# 08_-_Microcontroller.net
KiCad netlist of a schematic drawn in Altium Designer
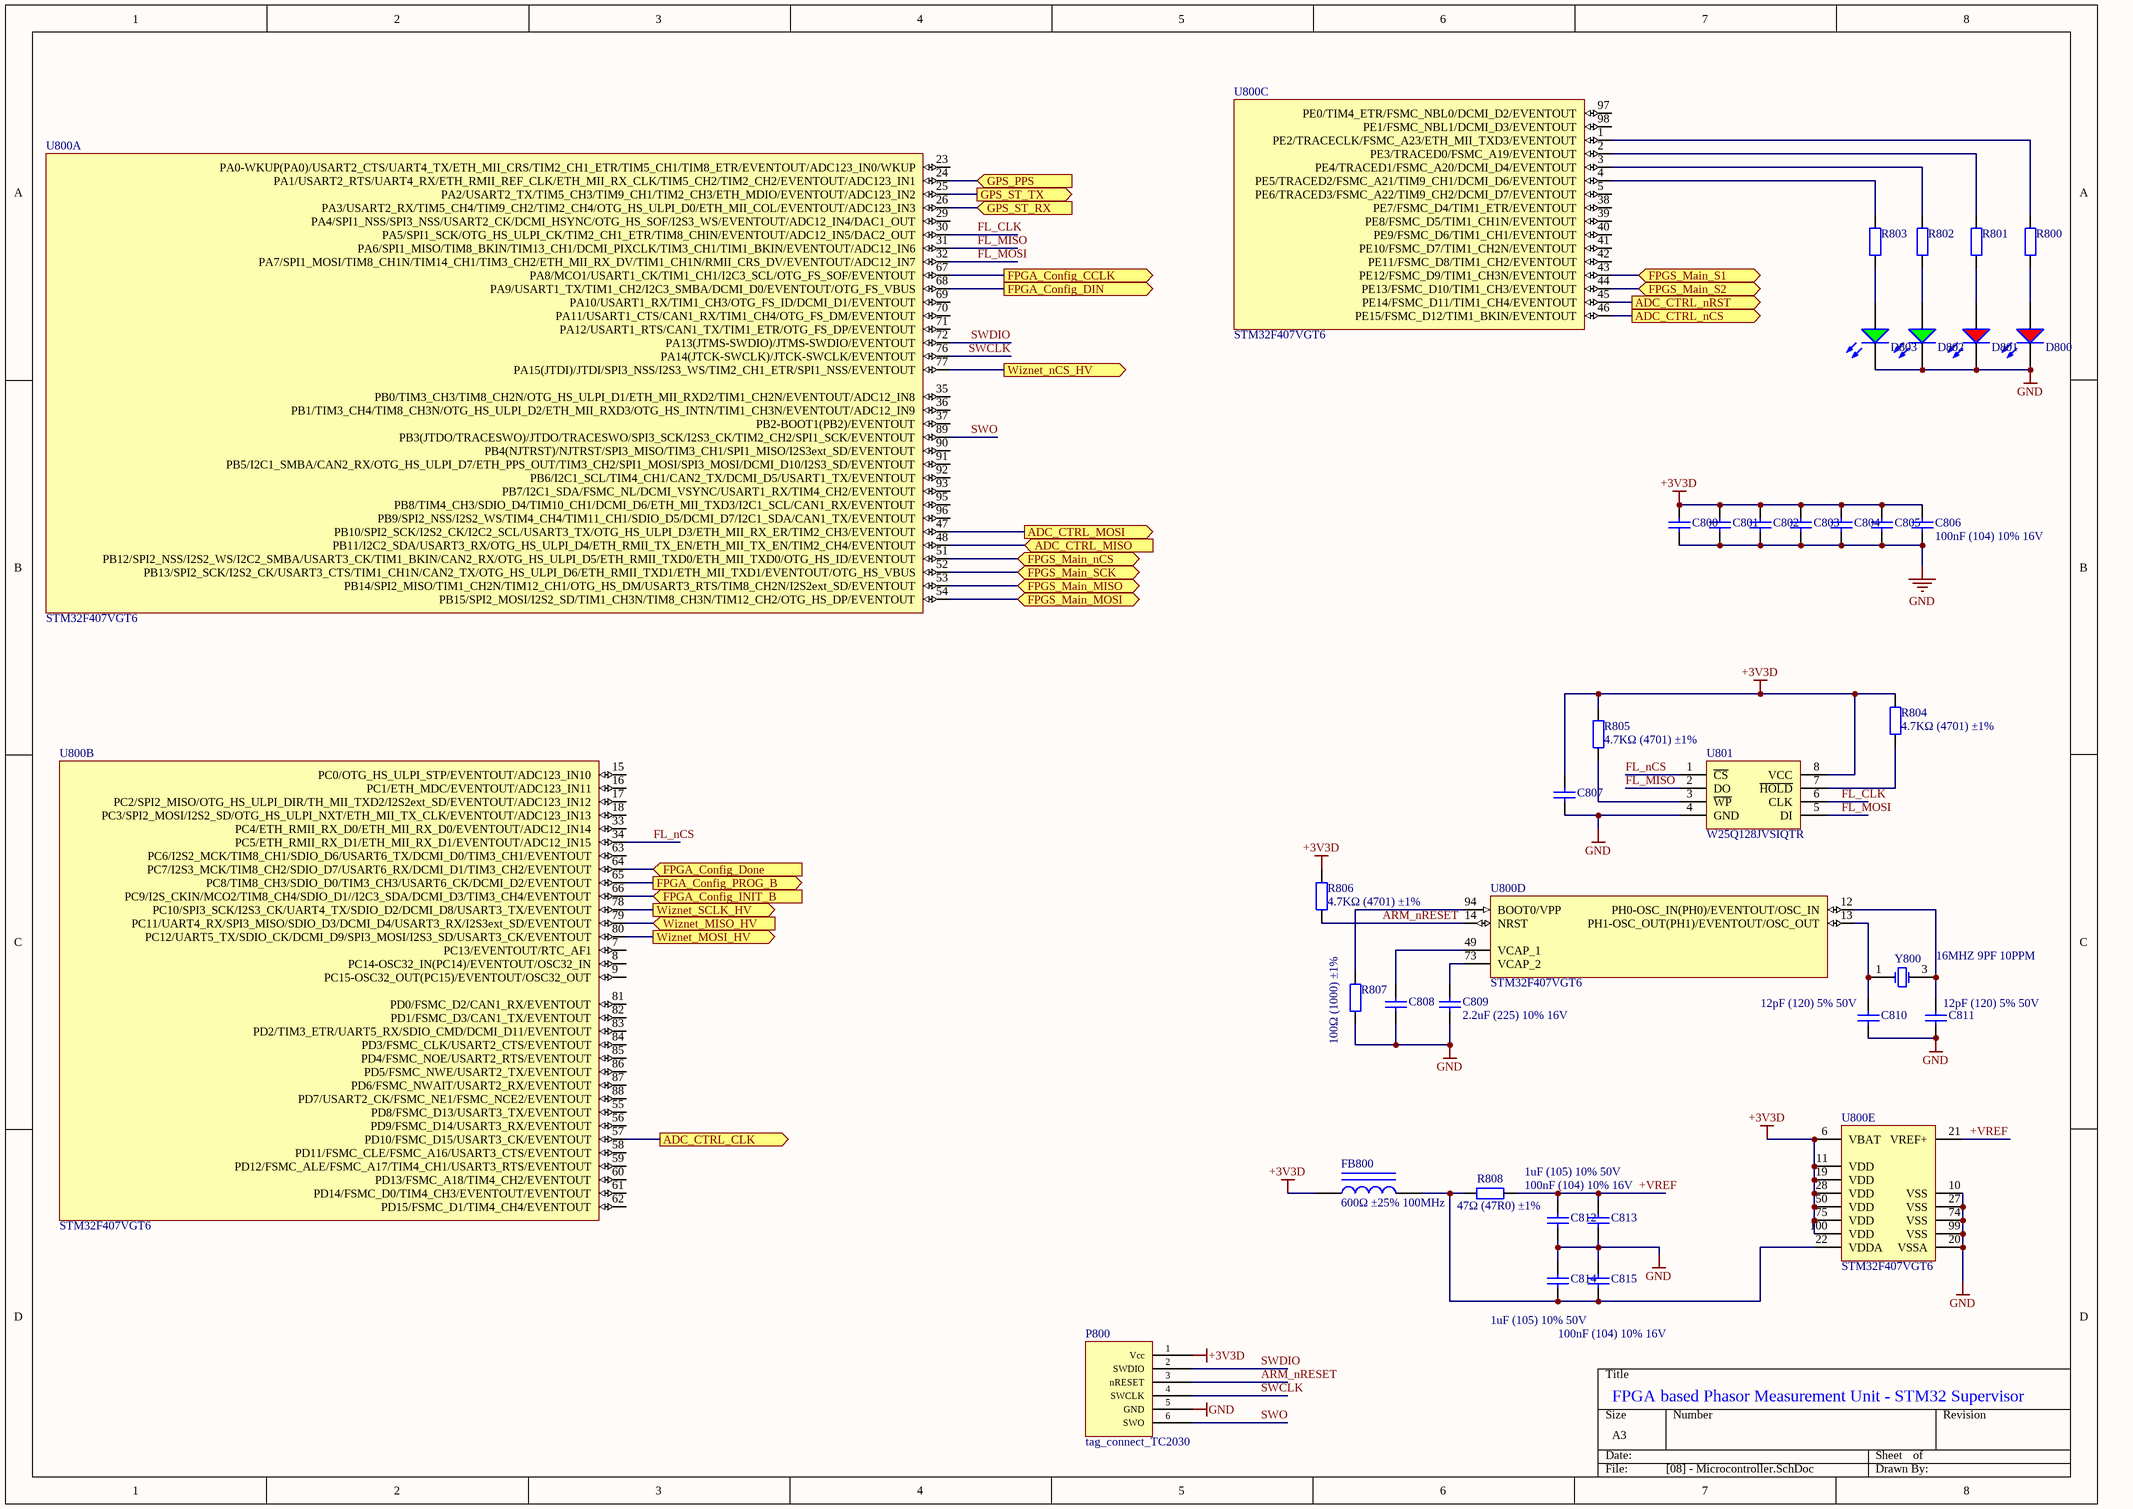
[diagram p0: [08] - Microcontroller.SchDoc]

(export (version "E")
  (design (tool "Eeschema 10.0.6"))
  (components
    (comp (ref "C800")
      (value "100nF (104) 10% 16V")
      (footprint "0402_C")
      (description "贴片电容")
      (libsource (lib "Cap") (part "0402 100nF (104) 10% 16V"))
    )
    (comp (ref "C801")
      (value "100nF (104) 10% 16V")
      (footprint "0402_C")
      (description "贴片电容")
      (libsource (lib "Cap") (part "0402 100nF (104) 10% 16V"))
    )
    (comp (ref "C802")
      (value "100nF (104) 10% 16V")
      (footprint "0402_C")
      (description "贴片电容")
      (libsource (lib "Cap") (part "0402 100nF (104) 10% 16V"))
    )
    (comp (ref "C803")
      (value "100nF (104) 10% 16V")
      (footprint "0402_C")
      (description "贴片电容")
      (libsource (lib "Cap") (part "0402 100nF (104) 10% 16V"))
    )
    (comp (ref "C804")
      (value "100nF (104) 10% 16V")
      (footprint "0402_C")
      (description "贴片电容")
      (libsource (lib "Cap") (part "0402 100nF (104) 10% 16V"))
    )
    (comp (ref "C805")
      (value "100nF (104) 10% 16V")
      (footprint "0402_C")
      (description "贴片电容")
      (libsource (lib "Cap") (part "0402 100nF (104) 10% 16V"))
    )
    (comp (ref "C806")
      (value "100nF (104) 10% 16V")
      (footprint "0402_C")
      (description "贴片电容")
      (libsource (lib "Cap") (part "0402 100nF (104) 10% 16V"))
    )
    (comp (ref "C807")
      (value "100nF (104) 10% 16V")
      (footprint "0402_C")
      (description "贴片电容")
      (libsource (lib "Cap") (part "0402 100nF (104) 10% 16V"))
    )
    (comp (ref "C808")
      (value "2.2uF (225) 10% 16V")
      (footprint "0603_C")
      (description "贴片电容")
      (libsource (lib "Cap") (part "0603 2.2uF (225) 10% 16V"))
    )
    (comp (ref "C809")
      (value "2.2uF (225) 10% 16V")
      (footprint "0603_C")
      (description "贴片电容")
      (libsource (lib "Cap") (part "0603 2.2uF (225) 10% 16V"))
    )
    (comp (ref "C810")
      (value "12pF (120) 5% 50V")
      (footprint "0402_C")
      (description "贴片电容")
      (libsource (lib "Cap") (part "0402 12pF (120) 5% 50V"))
    )
    (comp (ref "C811")
      (value "12pF (120) 5% 50V")
      (footprint "0402_C")
      (description "贴片电容")
      (libsource (lib "Cap") (part "0402 12pF (120) 5% 50V"))
    )
    (comp (ref "C812")
      (value "1uF (105) 10% 50V")
      (footprint "0603_C")
      (description "贴片电容")
      (libsource (lib "Cap") (part "0603 1uF (105) 10% 50V"))
    )
    (comp (ref "C813")
      (value "100nF (104) 10% 16V")
      (footprint "0402_C")
      (description "贴片电容")
      (libsource (lib "Cap") (part "0402 100nF (104) 10% 16V"))
    )
    (comp (ref "C814")
      (value "1uF (105) 10% 50V")
      (footprint "0603_C")
      (description "贴片电容")
      (libsource (lib "Cap") (part "0603 1uF (105) 10% 50V"))
    )
    (comp (ref "C815")
      (value "100nF (104) 10% 16V")
      (footprint "0402_C")
      (description "贴片电容")
      (libsource (lib "Cap") (part "0402 100nF (104) 10% 16V"))
    )
    (comp (ref "D800")
      (value "红灯 0603")
      (footprint "0603_LED_S1")
      (description "发光二极管")
      (libsource (lib "LED") (part "0603 红灯"))
    )
    (comp (ref "D801")
      (value "红灯 0603")
      (footprint "0603_LED_S1")
      (description "发光二极管")
      (libsource (lib "LED") (part "0603 红灯"))
    )
    (comp (ref "D802")
      (value "绿灯 0603")
      (footprint "0603_LED_S1")
      (description "发光二极管")
      (libsource (lib "LED") (part "0603 绿灯"))
    )
    (comp (ref "D803")
      (value "绿灯 0603")
      (footprint "0603_LED_S1")
      (description "发光二极管")
      (libsource (lib "LED") (part "0603 绿灯"))
    )
    (comp (ref "FB800")
      (value "600Ω ±25% 100MHz")
      (footprint "0805_L")
      (description "贴片磁珠")
      (libsource (lib "IUD") (part "0805 600Ω 25% 100MHz"))
    )
    (comp (ref "P800")
      (value "tag_connect_TC2030")
      (footprint "TC2030-MCP-NL")
      (libsource (lib "FPGA_PMU_lib") (part "tag_connect_TC2030"))
    )
    (comp (ref "R800")
      (value "150Ω (1500) ±1%")
      (footprint "0402_R")
      (description "贴片电阻")
      (libsource (lib "RES") (part "0402 150Ω (1500) 1%"))
    )
    (comp (ref "R801")
      (value "150Ω (1500) ±1%")
      (footprint "0402_R")
      (description "贴片电阻")
      (libsource (lib "RES") (part "0402 150Ω (1500) 1%"))
    )
    (comp (ref "R802")
      (value "150Ω (1500) ±1%")
      (footprint "0402_R")
      (description "贴片电阻")
      (libsource (lib "RES") (part "0402 150Ω (1500) 1%"))
    )
    (comp (ref "R803")
      (value "150Ω (1500) ±1%")
      (footprint "0402_R")
      (description "贴片电阻")
      (libsource (lib "RES") (part "0402 150Ω (1500) 1%"))
    )
    (comp (ref "R804")
      (value "4.7KΩ (4701) ±1%")
      (footprint "0402_R")
      (description "贴片电阻")
      (libsource (lib "") (part "0402 4.7KΩ (4701) 1%_1"))
    )
    (comp (ref "R805")
      (value "4.7KΩ (4701) ±1%")
      (footprint "0402_R")
      (description "贴片电阻")
      (libsource (lib "RES") (part "0402 4.7KΩ (4701) 1%"))
    )
    (comp (ref "R806")
      (value "4.7KΩ (4701) ±1%")
      (footprint "0402_R")
      (description "贴片电阻")
      (libsource (lib "") (part "0402 4.7KΩ (4701) 1%_1"))
    )
    (comp (ref "R807")
      (value "100Ω (1000) ±1%")
      (footprint "0402_R")
      (description "贴片电阻")
      (libsource (lib "RES") (part "0402 100Ω (1000) 1%"))
    )
    (comp (ref "R808")
      (value "47Ω (47R0) ±1%")
      (footprint "0402_R")
      (description "贴片电阻")
      (libsource (lib "RES") (part "0402 47Ω (47R0) 1%"))
    )
    (comp (ref "U800")
      (value "STM32F407VGT6")
      (footprint "LQFP-100_14x14x05P")
      (description "ARM")
      (libsource (lib "MCU") (part "STM32F407VGT6"))
    )
    (comp (ref "U801")
      (value "W25Q128JVSIQTR")
      (footprint "SOIC-8_208mil")
      (description "Flash ROM")
      (libsource (lib "IC") (part "W25Q128JVSIQTR_[C97521]"))
    )
    (comp (ref "Y800")
      (value "16MHZ 9PF 10PPM")
      (footprint "SMD-3225_4P")
      (description "贴片晶振")
      (libsource (lib "CrystalOscillator") (part "SMD-3225_4P  16MHZ 9PF 10PPM"))
    )
  )
  (nets
    (net (code "1") (name "+3V3D") (class "Default")
      (node (ref "C800") (pin "2") (pinfunction "2_2") (pintype "passive"))
      (node (ref "C801") (pin "2") (pinfunction "2_2") (pintype "passive"))
      (node (ref "C802") (pin "2") (pinfunction "2_2") (pintype "passive"))
      (node (ref "C803") (pin "2") (pinfunction "2_2") (pintype "passive"))
      (node (ref "C804") (pin "2") (pinfunction "2_2") (pintype "passive"))
      (node (ref "C805") (pin "2") (pinfunction "2_2") (pintype "passive"))
      (node (ref "C806") (pin "2") (pinfunction "2_2") (pintype "passive"))
      (node (ref "C807") (pin "2") (pinfunction "2_2") (pintype "passive"))
      (node (ref "FB800") (pin "1") (pinfunction "1_1") (pintype "passive"))
      (node (ref "P800") (pin "1") (pinfunction "Vcc_1") (pintype "passive"))
      (node (ref "R804") (pin "2") (pinfunction "2_2") (pintype "passive"))
      (node (ref "R805") (pin "1") (pinfunction "1_1") (pintype "passive"))
      (node (ref "R806") (pin "2") (pinfunction "2_2") (pintype "passive"))
      (node (ref "U800") (pin "100") (pinfunction "VDD_100") (pintype "power_in"))
      (node (ref "U800") (pin "11") (pinfunction "VDD_11") (pintype "power_in"))
      (node (ref "U800") (pin "19") (pinfunction "VDD_19") (pintype "power_in"))
      (node (ref "U800") (pin "28") (pinfunction "VDD_28") (pintype "power_in"))
      (node (ref "U800") (pin "50") (pinfunction "VDD_50") (pintype "power_in"))
      (node (ref "U800") (pin "6") (pinfunction "VBAT_6") (pintype "power_in"))
      (node (ref "U800") (pin "75") (pinfunction "VDD_75") (pintype "power_in"))
      (node (ref "U801") (pin "8") (pinfunction "VCC_8") (pintype "passive"))
    )
    (net (code "2") (name "/+VREF") (class "Default")
      (node (ref "C812") (pin "2") (pinfunction "2_2") (pintype "passive"))
      (node (ref "C813") (pin "2") (pinfunction "2_2") (pintype "passive"))
      (node (ref "R808") (pin "2") (pinfunction "2_2") (pintype "passive"))
      (node (ref "U800") (pin "21") (pinfunction "VREF+_21") (pintype "power_in"))
    )
    (net (code "3") (name "/ADC_CTRL_CLK") (class "Default")
      (node (ref "U800") (pin "57") (pinfunction "PD10/FSMC_D15/USART3_CK/EVENTOUT_57") (pintype "bidirectional"))
    )
    (net (code "4") (name "/ADC_CTRL_MISO") (class "Default")
      (node (ref "U800") (pin "48") (pinfunction "PB11/I2C2_SDA/USART3_RX/OTG_HS_ULPI_D4/ETH_RMII_TX_EN/ETH_MII_TX_EN/TIM2_CH4/EVENTOUT_48") (pintype "bidirectional"))
    )
    (net (code "5") (name "/ADC_CTRL_MOSI") (class "Default")
      (node (ref "U800") (pin "47") (pinfunction "PB10/SPI2_SCK/I2S2_CK/I2C2_SCL/USART3_TX/OTG_HS_ULPI_D3/ETH_MII_RX_ER/TIM2_CH3/EVENTOUT_47") (pintype "bidirectional"))
    )
    (net (code "6") (name "/ADC_CTRL_nCS") (class "Default")
      (node (ref "U800") (pin "46") (pinfunction "PE15/FSMC_D12/TIM1_BKIN/EVENTOUT_46") (pintype "bidirectional"))
    )
    (net (code "7") (name "/ADC_CTRL_nRST") (class "Default")
      (node (ref "U800") (pin "45") (pinfunction "PE14/FSMC_D11/TIM1_CH4/EVENTOUT_45") (pintype "bidirectional"))
    )
    (net (code "8") (name "/ARM_nRESET") (class "Default")
      (node (ref "P800") (pin "3") (pinfunction "nRESET_3") (pintype "passive"))
      (node (ref "R806") (pin "1") (pinfunction "1_1") (pintype "passive"))
      (node (ref "U800") (pin "14") (pinfunction "NRST_14") (pintype "bidirectional"))
    )
    (net (code "9") (name "/FL_CLK") (class "Default")
      (node (ref "U800") (pin "30") (pinfunction "PA5/SPI1_SCK/OTG_HS_ULPI_CK/TIM2_CH1_ETR/TIM8_CHIN/EVENTOUT/ADC12_IN5/DAC2_OUT_30") (pintype "bidirectional"))
      (node (ref "U801") (pin "6") (pinfunction "CLK_6") (pintype "passive"))
    )
    (net (code "10") (name "/FL_MISO") (class "Default")
      (node (ref "U800") (pin "31") (pinfunction "PA6/SPI1_MISO/TIM8_BKIN/TIM13_CH1/DCMI_PIXCLK/TIM3_CH1/TIM1_BKIN/EVENTOUT/ADC12_IN6_31") (pintype "bidirectional"))
      (node (ref "U801") (pin "2") (pinfunction "DO_2") (pintype "passive"))
    )
    (net (code "11") (name "/FL_MOSI") (class "Default")
      (node (ref "U800") (pin "32") (pinfunction "PA7/SPI1_MOSI/TIM8_CH1N/TIM14_CH1/TIM3_CH2/ETH_MII_RX_DV/TIM1_CH1N/RMII_CRS_DV/EVENTOUT/ADC12_IN7_32") (pintype "bidirectional"))
      (node (ref "U801") (pin "5") (pinfunction "DI_5") (pintype "passive"))
    )
    (net (code "12") (name "/FL_nCS") (class "Default")
      (node (ref "U800") (pin "34") (pinfunction "PC5/ETH_RMII_RX_D1/ETH_MII_RX_D1/EVENTOUT/ADC12_IN15_34") (pintype "bidirectional"))
      (node (ref "U801") (pin "1") (pinfunction "~{CS}_1") (pintype "passive"))
    )
    (net (code "13") (name "/FPGA_Config_CCLK") (class "Default")
      (node (ref "U800") (pin "67") (pinfunction "PA8/MCO1/USART1_CK/TIM1_CH1/I2C3_SCL/OTG_FS_SOF/EVENTOUT_67") (pintype "bidirectional"))
    )
    (net (code "14") (name "/FPGA_Config_DIN") (class "Default")
      (node (ref "U800") (pin "68") (pinfunction "PA9/USART1_TX/TIM1_CH2/I2C3_SMBA/DCMI_D0/EVENTOUT/OTG_FS_VBUS_68") (pintype "bidirectional"))
    )
    (net (code "15") (name "/FPGA_Config_Done") (class "Default")
      (node (ref "U800") (pin "64") (pinfunction "PC7/I2S3_MCK/TIM8_CH2/SDIO_D7/USART6_RX/DCMI_D1/TIM3_CH2/EVENTOUT_64") (pintype "bidirectional"))
    )
    (net (code "16") (name "/FPGA_Config_INIT_B") (class "Default")
      (node (ref "U800") (pin "66") (pinfunction "PC9/I2S_CKIN/MCO2/TIM8_CH4/SDIO_D1//I2C3_SDA/DCMI_D3/TIM3_CH4/EVENTOUT_66") (pintype "bidirectional"))
    )
    (net (code "17") (name "/FPGA_Config_PROG_B") (class "Default")
      (node (ref "U800") (pin "65") (pinfunction "PC8/TIM8_CH3/SDIO_D0/TIM3_CH3/USART6_CK/DCMI_D2/EVENTOUT_65") (pintype "bidirectional"))
    )
    (net (code "18") (name "/FPGS_Main_MISO") (class "Default")
      (node (ref "U800") (pin "53") (pinfunction "PB14/SPI2_MISO/TIM1_CH2N/TIM12_CH1/OTG_HS_DM/USART3_RTS/TIM8_CH2N/I2S2ext_SD/EVENTOUT_53") (pintype "bidirectional"))
    )
    (net (code "19") (name "/FPGS_Main_MOSI") (class "Default")
      (node (ref "U800") (pin "54") (pinfunction "PB15/SPI2_MOSI/I2S2_SD/TIM1_CH3N/TIM8_CH3N/TIM12_CH2/OTG_HS_DP/EVENTOUT_54") (pintype "bidirectional"))
    )
    (net (code "20") (name "/FPGS_Main_S1") (class "Default")
      (node (ref "U800") (pin "43") (pinfunction "PE12/FSMC_D9/TIM1_CH3N/EVENTOUT_43") (pintype "bidirectional"))
    )
    (net (code "21") (name "/FPGS_Main_S2") (class "Default")
      (node (ref "U800") (pin "44") (pinfunction "PE13/FSMC_D10/TIM1_CH3/EVENTOUT_44") (pintype "bidirectional"))
    )
    (net (code "22") (name "/FPGS_Main_SCK") (class "Default")
      (node (ref "U800") (pin "52") (pinfunction "PB13/SPI2_SCK/I2S2_CK/USART3_CTS/TIM1_CH1N/CAN2_TX/OTG_HS_ULPI_D6/ETH_RMII_TXD1/ETH_MII_TXD1/EVENTOUT/OTG_HS_VBUS_52") (pintype "bidirectional"))
    )
    (net (code "23") (name "/FPGS_Main_nCS") (class "Default")
      (node (ref "U800") (pin "51") (pinfunction "PB12/SPI2_NSS/I2S2_WS/I2C2_SMBA/USART3_CK/TIM1_BKIN/CAN2_RX/OTG_HS_ULPI_D5/ETH_RMII_TXD0/ETH_MII_TXD0/OTG_HS_ID/EVENTOUT_51") (pintype "bidirectional"))
    )
    (net (code "24") (name "/GPS_PPS") (class "Default")
      (node (ref "U800") (pin "24") (pinfunction "PA1/USART2_RTS/UART4_RX/ETH_RMII_REF_CLK/ETH_MII_RX_CLK/TIM5_CH2/TIM2_CH2/EVENTOUT/ADC123_IN1_24") (pintype "bidirectional"))
    )
    (net (code "25") (name "/GPS_ST_RX") (class "Default")
      (node (ref "U800") (pin "26") (pinfunction "PA3/USART2_RX/TIM5_CH4/TIM9_CH2/TIM2_CH4/OTG_HS_ULPI_D0/ETH_MII_COL/EVENTOUT/ADC123_IN3_26") (pintype "bidirectional"))
    )
    (net (code "26") (name "/GPS_ST_TX") (class "Default")
      (node (ref "U800") (pin "25") (pinfunction "PA2/USART2_TX/TIM5_CH3/TIM9_CH1/TIM2_CH3/ETH_MDIO/EVENTOUT/ADC123_IN2_25") (pintype "bidirectional"))
    )
    (net (code "27") (name "/SWCLK") (class "Default")
      (node (ref "P800") (pin "4") (pinfunction "SWCLK_4") (pintype "passive"))
      (node (ref "U800") (pin "76") (pinfunction "PA14(JTCK-SWCLK)/JTCK-SWCLK/EVENTOUT_76") (pintype "bidirectional"))
    )
    (net (code "28") (name "/SWDIO") (class "Default")
      (node (ref "P800") (pin "2") (pinfunction "SWDIO_2") (pintype "passive"))
      (node (ref "U800") (pin "72") (pinfunction "PA13(JTMS-SWDIO)/JTMS-SWDIO/EVENTOUT_72") (pintype "bidirectional"))
    )
    (net (code "29") (name "/SWO") (class "Default")
      (node (ref "P800") (pin "6") (pinfunction "SWO_6") (pintype "passive"))
      (node (ref "U800") (pin "89") (pinfunction "PB3(JTDO/TRACESWO)/JTDO/TRACESWO/SPI3_SCK/I2S3_CK/TIM2_CH2/SPI1_SCK/EVENTOUT_89") (pintype "bidirectional"))
    )
    (net (code "30") (name "/Wiznet_MISO_HV") (class "Default")
      (node (ref "U800") (pin "79") (pinfunction "PC11/UART4_RX/SPI3_MISO/SDIO_D3/DCMI_D4/USART3_RX/I2S3ext_SD/EVENTOUT_79") (pintype "bidirectional"))
    )
    (net (code "31") (name "/Wiznet_MOSI_HV") (class "Default")
      (node (ref "U800") (pin "80") (pinfunction "PC12/UART5_TX/SDIO_CK/DCMI_D9/SPI3_MOSI/I2S3_SD/USART3_CK/EVENTOUT_80") (pintype "bidirectional"))
    )
    (net (code "32") (name "/Wiznet_SCLK_HV") (class "Default")
      (node (ref "U800") (pin "78") (pinfunction "PC10/SPI3_SCK/I2S3_CK/UART4_TX/SDIO_D2/DCMI_D8/USART3_TX/EVENTOUT_78") (pintype "bidirectional"))
    )
    (net (code "33") (name "/Wiznet_nCS_HV") (class "Default")
      (node (ref "U800") (pin "77") (pinfunction "PA15(JTDI)/JTDI/SPI3_NSS/I2S3_WS/TIM2_CH1_ETR/SPI1_NSS/EVENTOUT_77") (pintype "bidirectional"))
    )
    (net (code "34") (name "GND") (class "Default")
      (node (ref "C800") (pin "1") (pinfunction "1_1") (pintype "passive"))
      (node (ref "C801") (pin "1") (pinfunction "1_1") (pintype "passive"))
      (node (ref "C802") (pin "1") (pinfunction "1_1") (pintype "passive"))
      (node (ref "C803") (pin "1") (pinfunction "1_1") (pintype "passive"))
      (node (ref "C804") (pin "1") (pinfunction "1_1") (pintype "passive"))
      (node (ref "C805") (pin "1") (pinfunction "1_1") (pintype "passive"))
      (node (ref "C806") (pin "1") (pinfunction "1_1") (pintype "passive"))
      (node (ref "C807") (pin "1") (pinfunction "1_1") (pintype "passive"))
      (node (ref "C808") (pin "1") (pinfunction "1_1") (pintype "passive"))
      (node (ref "C809") (pin "1") (pinfunction "1_1") (pintype "passive"))
      (node (ref "C810") (pin "2") (pinfunction "2_2") (pintype "passive"))
      (node (ref "C811") (pin "2") (pinfunction "2_2") (pintype "passive"))
      (node (ref "C812") (pin "1") (pinfunction "1_1") (pintype "passive"))
      (node (ref "C813") (pin "1") (pinfunction "1_1") (pintype "passive"))
      (node (ref "C814") (pin "2") (pinfunction "2_2") (pintype "passive"))
      (node (ref "C815") (pin "2") (pinfunction "2_2") (pintype "passive"))
      (node (ref "D800") (pin "K") (pinfunction "K_K") (pintype "passive"))
      (node (ref "D801") (pin "K") (pinfunction "K_K") (pintype "passive"))
      (node (ref "D802") (pin "K") (pinfunction "K_K") (pintype "passive"))
      (node (ref "D803") (pin "K") (pinfunction "K_K") (pintype "passive"))
      (node (ref "P800") (pin "5") (pinfunction "GND_5") (pintype "passive"))
      (node (ref "R807") (pin "1") (pinfunction "1_1") (pintype "passive"))
      (node (ref "U800") (pin "10") (pinfunction "VSS_10") (pintype "power_in"))
      (node (ref "U800") (pin "20") (pinfunction "VSSA_20") (pintype "power_in"))
      (node (ref "U800") (pin "27") (pinfunction "VSS_27") (pintype "power_in"))
      (node (ref "U800") (pin "74") (pinfunction "VSS_74") (pintype "power_in"))
      (node (ref "U800") (pin "99") (pinfunction "VSS_99") (pintype "power_in"))
      (node (ref "U801") (pin "4") (pinfunction "GND_4") (pintype "passive"))
    )
    (net (code "35") (name "Net-(D800-PadA)") (class "Default")
      (node (ref "D800") (pin "A") (pinfunction "A_A") (pintype "passive"))
      (node (ref "R800") (pin "1") (pinfunction "1_1") (pintype "passive"))
    )
    (net (code "36") (name "Net-(D801-PadA)") (class "Default")
      (node (ref "D801") (pin "A") (pinfunction "A_A") (pintype "passive"))
      (node (ref "R801") (pin "1") (pinfunction "1_1") (pintype "passive"))
    )
    (net (code "37") (name "Net-(D802-PadA)") (class "Default")
      (node (ref "D802") (pin "A") (pinfunction "A_A") (pintype "passive"))
      (node (ref "R802") (pin "1") (pinfunction "1_1") (pintype "passive"))
    )
    (net (code "38") (name "Net-(D803-PadA)") (class "Default")
      (node (ref "D803") (pin "A") (pinfunction "A_A") (pintype "passive"))
      (node (ref "R803") (pin "1") (pinfunction "1_1") (pintype "passive"))
    )
    (net (code "39") (name "Net-(U800C-PE2{slash}TRACECLK{slash}FSMC_A23{slash}ETH_MII_TXD3{slash}EVENTOUT)") (class "Default")
      (node (ref "R800") (pin "2") (pinfunction "2_2") (pintype "passive"))
      (node (ref "U800") (pin "1") (pinfunction "PE2/TRACECLK/FSMC_A23/ETH_MII_TXD3/EVENTOUT_1") (pintype "bidirectional"))
    )
    (net (code "40") (name "Net-(U800C-PE3{slash}TRACED0{slash}FSMC_A19{slash}EVENTOUT)") (class "Default")
      (node (ref "R801") (pin "2") (pinfunction "2_2") (pintype "passive"))
      (node (ref "U800") (pin "2") (pinfunction "PE3/TRACED0/FSMC_A19/EVENTOUT_2") (pintype "bidirectional"))
    )
    (net (code "41") (name "Net-(U800C-PE4{slash}TRACED1{slash}FSMC_A20{slash}DCMI_D4{slash}EVENTOUT)") (class "Default")
      (node (ref "R802") (pin "2") (pinfunction "2_2") (pintype "passive"))
      (node (ref "U800") (pin "3") (pinfunction "PE4/TRACED1/FSMC_A20/DCMI_D4/EVENTOUT_3") (pintype "bidirectional"))
    )
    (net (code "42") (name "Net-(U800C-PE5{slash}TRACED2{slash}FSMC_A21{slash}TIM9_CH1{slash}DCMI_D6{slash}EVENTOUT)") (class "Default")
      (node (ref "R803") (pin "2") (pinfunction "2_2") (pintype "passive"))
      (node (ref "U800") (pin "4") (pinfunction "PE5/TRACED2/FSMC_A21/TIM9_CH1/DCMI_D6/EVENTOUT_4") (pintype "bidirectional"))
    )
    (net (code "43") (name "Net-(U800D-BOOT0{slash}VPP)") (class "Default")
      (node (ref "R807") (pin "2") (pinfunction "2_2") (pintype "passive"))
      (node (ref "U800") (pin "94") (pinfunction "BOOT0/VPP_94") (pintype "input"))
    )
    (net (code "44") (name "Net-(U800D-PH0-OSC_IN(PH0){slash}EVENTOUT{slash}OSC_IN)") (class "Default")
      (node (ref "C811") (pin "1") (pinfunction "1_1") (pintype "passive"))
      (node (ref "U800") (pin "12") (pinfunction "PH0-OSC_IN(PH0)/EVENTOUT/OSC_IN_12") (pintype "bidirectional"))
      (node (ref "Y800") (pin "3") (pinfunction "OSC2_3") (pintype "passive"))
    )
    (net (code "45") (name "Net-(U800D-PH1-OSC_OUT(PH1){slash}EVENTOUT{slash}OSC_OUT)") (class "Default")
      (node (ref "C810") (pin "1") (pinfunction "1_1") (pintype "passive"))
      (node (ref "U800") (pin "13") (pinfunction "PH1-OSC_OUT(PH1)/EVENTOUT/OSC_OUT_13") (pintype "bidirectional"))
      (node (ref "Y800") (pin "1") (pinfunction "OSC1_1") (pintype "passive"))
    )
    (net (code "46") (name "Net-(U800D-VCAP_1)") (class "Default")
      (node (ref "C808") (pin "2") (pinfunction "2_2") (pintype "passive"))
      (node (ref "U800") (pin "49") (pinfunction "VCAP_1_49") (pintype "power_in"))
    )
    (net (code "47") (name "Net-(U800D-VCAP_2)") (class "Default")
      (node (ref "C809") (pin "2") (pinfunction "2_2") (pintype "passive"))
      (node (ref "U800") (pin "73") (pinfunction "VCAP_2_73") (pintype "power_in"))
    )
    (net (code "48") (name "Net-(U800E-VDDA)") (class "Default")
      (node (ref "C814") (pin "1") (pinfunction "1_1") (pintype "passive"))
      (node (ref "C815") (pin "1") (pinfunction "1_1") (pintype "passive"))
      (node (ref "FB800") (pin "2") (pinfunction "2_2") (pintype "passive"))
      (node (ref "R808") (pin "1") (pinfunction "1_1") (pintype "passive"))
      (node (ref "U800") (pin "22") (pinfunction "VDDA_22") (pintype "power_in"))
    )
    (net (code "49") (name "Net-(U801-~{HOLD})") (class "Default")
      (node (ref "R804") (pin "1") (pinfunction "1_1") (pintype "passive"))
      (node (ref "U801") (pin "7") (pinfunction "~{HOLD}_7") (pintype "passive"))
    )
    (net (code "50") (name "Net-(U801-~{WP})") (class "Default")
      (node (ref "R805") (pin "2") (pinfunction "2_2") (pintype "passive"))
      (node (ref "U801") (pin "3") (pinfunction "~{WP}_3") (pintype "passive"))
    )
    (net (code "51") (name "unconnected-(U800A-PA0-WKUP(PA0){slash}USART2_CTS{slash}UART4_TX{slash}ETH_MII_CRS{slash}TIM2_CH1_ETR{slash}TIM5_CH1{slash}TIM8_ETR{slash}EVENTOUT{slash}ADC123_IN0{slash}WKUP-Pad23)") (class "Default")
      (node (ref "U800") (pin "23") (pinfunction "PA0-WKUP(PA0)/USART2_CTS/UART4_TX/ETH_MII_CRS/TIM2_CH1_ETR/TIM5_CH1/TIM8_ETR/EVENTOUT/ADC123_IN0/WKUP_23") (pintype "bidirectional"))
    )
    (net (code "52") (name "unconnected-(U800A-PA4{slash}SPI1_NSS{slash}SPI3_NSS{slash}USART2_CK{slash}DCMI_HSYNC{slash}OTG_HS_SOF{slash}I2S3_WS{slash}EVENTOUT{slash}ADC12_IN4{slash}DAC1_OUT-Pad29)") (class "Default")
      (node (ref "U800") (pin "29") (pinfunction "PA4/SPI1_NSS/SPI3_NSS/USART2_CK/DCMI_HSYNC/OTG_HS_SOF/I2S3_WS/EVENTOUT/ADC12_IN4/DAC1_OUT_29") (pintype "bidirectional"))
    )
    (net (code "53") (name "unconnected-(U800A-PA10{slash}USART1_RX{slash}TIM1_CH3{slash}OTG_FS_ID{slash}DCMI_D1{slash}EVENTOUT-Pad69)") (class "Default")
      (node (ref "U800") (pin "69") (pinfunction "PA10/USART1_RX/TIM1_CH3/OTG_FS_ID/DCMI_D1/EVENTOUT_69") (pintype "bidirectional"))
    )
    (net (code "54") (name "unconnected-(U800A-PA11{slash}USART1_CTS{slash}CAN1_RX{slash}TIM1_CH4{slash}OTG_FS_DM{slash}EVENTOUT-Pad70)") (class "Default")
      (node (ref "U800") (pin "70") (pinfunction "PA11/USART1_CTS/CAN1_RX/TIM1_CH4/OTG_FS_DM/EVENTOUT_70") (pintype "bidirectional"))
    )
    (net (code "55") (name "unconnected-(U800A-PA12{slash}USART1_RTS{slash}CAN1_TX{slash}TIM1_ETR{slash}OTG_FS_DP{slash}EVENTOUT-Pad71)") (class "Default")
      (node (ref "U800") (pin "71") (pinfunction "PA12/USART1_RTS/CAN1_TX/TIM1_ETR/OTG_FS_DP/EVENTOUT_71") (pintype "bidirectional"))
    )
    (net (code "56") (name "unconnected-(U800A-PB0{slash}TIM3_CH3{slash}TIM8_CH2N{slash}OTG_HS_ULPI_D1{slash}ETH_MII_RXD2{slash}TIM1_CH2N{slash}EVENTOUT{slash}ADC12_IN8-Pad35)") (class "Default")
      (node (ref "U800") (pin "35") (pinfunction "PB0/TIM3_CH3/TIM8_CH2N/OTG_HS_ULPI_D1/ETH_MII_RXD2/TIM1_CH2N/EVENTOUT/ADC12_IN8_35") (pintype "bidirectional"))
    )
    (net (code "57") (name "unconnected-(U800A-PB1{slash}TIM3_CH4{slash}TIM8_CH3N{slash}OTG_HS_ULPI_D2{slash}ETH_MII_RXD3{slash}OTG_HS_INTN{slash}TIM1_CH3N{slash}EVENTOUT{slash}ADC12_IN9-Pad36)") (class "Default")
      (node (ref "U800") (pin "36") (pinfunction "PB1/TIM3_CH4/TIM8_CH3N/OTG_HS_ULPI_D2/ETH_MII_RXD3/OTG_HS_INTN/TIM1_CH3N/EVENTOUT/ADC12_IN9_36") (pintype "bidirectional"))
    )
    (net (code "58") (name "unconnected-(U800A-PB2-BOOT1(PB2){slash}EVENTOUT-Pad37)") (class "Default")
      (node (ref "U800") (pin "37") (pinfunction "PB2-BOOT1(PB2)/EVENTOUT_37") (pintype "bidirectional"))
    )
    (net (code "59") (name "unconnected-(U800A-PB4(NJTRST){slash}NJTRST{slash}SPI3_MISO{slash}TIM3_CH1{slash}SPI1_MISO{slash}I2S3ext_SD{slash}EVENTOUT-Pad90)") (class "Default")
      (node (ref "U800") (pin "90") (pinfunction "PB4(NJTRST)/NJTRST/SPI3_MISO/TIM3_CH1/SPI1_MISO/I2S3ext_SD/EVENTOUT_90") (pintype "bidirectional"))
    )
    (net (code "60") (name "unconnected-(U800A-PB5{slash}I2C1_SMBA{slash}CAN2_RX{slash}OTG_HS_ULPI_D7{slash}ETH_PPS_OUT{slash}TIM3_CH2{slash}SPI1_MOSI{slash}SPI3_MOSI{slash}DCMI_D10{slash}I2S3_SD{slash}EVENTOUT-Pad91)") (class "Default")
      (node (ref "U800") (pin "91") (pinfunction "PB5/I2C1_SMBA/CAN2_RX/OTG_HS_ULPI_D7/ETH_PPS_OUT/TIM3_CH2/SPI1_MOSI/SPI3_MOSI/DCMI_D10/I2S3_SD/EVENTOUT_91") (pintype "bidirectional"))
    )
    (net (code "61") (name "unconnected-(U800A-PB6{slash}I2C1_SCL{slash}TIM4_CH1{slash}CAN2_TX{slash}DCMI_D5{slash}USART1_TX{slash}EVENTOUT-Pad92)") (class "Default")
      (node (ref "U800") (pin "92") (pinfunction "PB6/I2C1_SCL/TIM4_CH1/CAN2_TX/DCMI_D5/USART1_TX/EVENTOUT_92") (pintype "bidirectional"))
    )
    (net (code "62") (name "unconnected-(U800A-PB7{slash}I2C1_SDA{slash}FSMC_NL{slash}DCMI_VSYNC{slash}USART1_RX{slash}TIM4_CH2{slash}EVENTOUT-Pad93)") (class "Default")
      (node (ref "U800") (pin "93") (pinfunction "PB7/I2C1_SDA/FSMC_NL/DCMI_VSYNC/USART1_RX/TIM4_CH2/EVENTOUT_93") (pintype "bidirectional"))
    )
    (net (code "63") (name "unconnected-(U800A-PB8{slash}TIM4_CH3{slash}SDIO_D4{slash}TIM10_CH1{slash}DCMI_D6{slash}ETH_MII_TXD3{slash}I2C1_SCL{slash}CAN1_RX{slash}EVENTOUT-Pad95)") (class "Default")
      (node (ref "U800") (pin "95") (pinfunction "PB8/TIM4_CH3/SDIO_D4/TIM10_CH1/DCMI_D6/ETH_MII_TXD3/I2C1_SCL/CAN1_RX/EVENTOUT_95") (pintype "bidirectional"))
    )
    (net (code "64") (name "unconnected-(U800A-PB9{slash}SPI2_NSS{slash}I2S2_WS{slash}TIM4_CH4{slash}TIM11_CH1{slash}SDIO_D5{slash}DCMI_D7{slash}I2C1_SDA{slash}CAN1_TX{slash}EVENTOUT-Pad96)") (class "Default")
      (node (ref "U800") (pin "96") (pinfunction "PB9/SPI2_NSS/I2S2_WS/TIM4_CH4/TIM11_CH1/SDIO_D5/DCMI_D7/I2C1_SDA/CAN1_TX/EVENTOUT_96") (pintype "bidirectional"))
    )
    (net (code "65") (name "unconnected-(U800B-PC0{slash}OTG_HS_ULPI_STP{slash}EVENTOUT{slash}ADC123_IN10-Pad15)") (class "Default")
      (node (ref "U800") (pin "15") (pinfunction "PC0/OTG_HS_ULPI_STP/EVENTOUT/ADC123_IN10_15") (pintype "bidirectional"))
    )
    (net (code "66") (name "unconnected-(U800B-PC1{slash}ETH_MDC{slash}EVENTOUT{slash}ADC123_IN11-Pad16)") (class "Default")
      (node (ref "U800") (pin "16") (pinfunction "PC1/ETH_MDC/EVENTOUT/ADC123_IN11_16") (pintype "bidirectional"))
    )
    (net (code "67") (name "unconnected-(U800B-PC2{slash}SPI2_MISO{slash}OTG_HS_ULPI_DIR{slash}TH_MII_TXD2{slash}I2S2ext_SD{slash}EVENTOUT{slash}ADC123_IN12-Pad17)") (class "Default")
      (node (ref "U800") (pin "17") (pinfunction "PC2/SPI2_MISO/OTG_HS_ULPI_DIR/TH_MII_TXD2/I2S2ext_SD/EVENTOUT/ADC123_IN12_17") (pintype "bidirectional"))
    )
    (net (code "68") (name "unconnected-(U800B-PC3{slash}SPI2_MOSI{slash}I2S2_SD{slash}OTG_HS_ULPI_NXT{slash}ETH_MII_TX_CLK{slash}EVENTOUT{slash}ADC123_IN13-Pad18)") (class "Default")
      (node (ref "U800") (pin "18") (pinfunction "PC3/SPI2_MOSI/I2S2_SD/OTG_HS_ULPI_NXT/ETH_MII_TX_CLK/EVENTOUT/ADC123_IN13_18") (pintype "bidirectional"))
    )
    (net (code "69") (name "unconnected-(U800B-PC4{slash}ETH_RMII_RX_D0{slash}ETH_MII_RX_D0{slash}EVENTOUT{slash}ADC12_IN14-Pad33)") (class "Default")
      (node (ref "U800") (pin "33") (pinfunction "PC4/ETH_RMII_RX_D0/ETH_MII_RX_D0/EVENTOUT/ADC12_IN14_33") (pintype "bidirectional"))
    )
    (net (code "70") (name "unconnected-(U800B-PC6{slash}I2S2_MCK{slash}TIM8_CH1{slash}SDIO_D6{slash}USART6_TX{slash}DCMI_D0{slash}TIM3_CH1{slash}EVENTOUT-Pad63)") (class "Default")
      (node (ref "U800") (pin "63") (pinfunction "PC6/I2S2_MCK/TIM8_CH1/SDIO_D6/USART6_TX/DCMI_D0/TIM3_CH1/EVENTOUT_63") (pintype "bidirectional"))
    )
    (net (code "71") (name "unconnected-(U800B-PC13{slash}EVENTOUT{slash}RTC_AF1-Pad7)") (class "Default")
      (node (ref "U800") (pin "7") (pinfunction "PC13/EVENTOUT/RTC_AF1_7") (pintype "bidirectional"))
    )
    (net (code "72") (name "unconnected-(U800B-PC14-OSC32_IN(PC14){slash}EVENTOUT{slash}OSC32_IN-Pad8)") (class "Default")
      (node (ref "U800") (pin "8") (pinfunction "PC14-OSC32_IN(PC14)/EVENTOUT/OSC32_IN_8") (pintype "bidirectional"))
    )
    (net (code "73") (name "unconnected-(U800B-PC15-OSC32_OUT(PC15){slash}EVENTOUT{slash}OSC32_OUT-Pad9)") (class "Default")
      (node (ref "U800") (pin "9") (pinfunction "PC15-OSC32_OUT(PC15)/EVENTOUT/OSC32_OUT_9") (pintype "bidirectional"))
    )
    (net (code "74") (name "unconnected-(U800B-PD0{slash}FSMC_D2{slash}CAN1_RX{slash}EVENTOUT-Pad81)") (class "Default")
      (node (ref "U800") (pin "81") (pinfunction "PD0/FSMC_D2/CAN1_RX/EVENTOUT_81") (pintype "bidirectional"))
    )
    (net (code "75") (name "unconnected-(U800B-PD1{slash}FSMC_D3{slash}CAN1_TX{slash}EVENTOUT-Pad82)") (class "Default")
      (node (ref "U800") (pin "82") (pinfunction "PD1/FSMC_D3/CAN1_TX/EVENTOUT_82") (pintype "bidirectional"))
    )
    (net (code "76") (name "unconnected-(U800B-PD2{slash}TIM3_ETR{slash}UART5_RX{slash}SDIO_CMD{slash}DCMI_D11{slash}EVENTOUT-Pad83)") (class "Default")
      (node (ref "U800") (pin "83") (pinfunction "PD2/TIM3_ETR/UART5_RX/SDIO_CMD/DCMI_D11/EVENTOUT_83") (pintype "bidirectional"))
    )
    (net (code "77") (name "unconnected-(U800B-PD3{slash}FSMC_CLK{slash}USART2_CTS{slash}EVENTOUT-Pad84)") (class "Default")
      (node (ref "U800") (pin "84") (pinfunction "PD3/FSMC_CLK/USART2_CTS/EVENTOUT_84") (pintype "bidirectional"))
    )
    (net (code "78") (name "unconnected-(U800B-PD4{slash}FSMC_NOE{slash}USART2_RTS{slash}EVENTOUT-Pad85)") (class "Default")
      (node (ref "U800") (pin "85") (pinfunction "PD4/FSMC_NOE/USART2_RTS/EVENTOUT_85") (pintype "bidirectional"))
    )
    (net (code "79") (name "unconnected-(U800B-PD5{slash}FSMC_NWE{slash}USART2_TX{slash}EVENTOUT-Pad86)") (class "Default")
      (node (ref "U800") (pin "86") (pinfunction "PD5/FSMC_NWE/USART2_TX/EVENTOUT_86") (pintype "bidirectional"))
    )
    (net (code "80") (name "unconnected-(U800B-PD6{slash}FSMC_NWAIT{slash}USART2_RX{slash}EVENTOUT-Pad87)") (class "Default")
      (node (ref "U800") (pin "87") (pinfunction "PD6/FSMC_NWAIT/USART2_RX/EVENTOUT_87") (pintype "bidirectional"))
    )
    (net (code "81") (name "unconnected-(U800B-PD7{slash}USART2_CK{slash}FSMC_NE1{slash}FSMC_NCE2{slash}EVENTOUT-Pad88)") (class "Default")
      (node (ref "U800") (pin "88") (pinfunction "PD7/USART2_CK/FSMC_NE1/FSMC_NCE2/EVENTOUT_88") (pintype "bidirectional"))
    )
    (net (code "82") (name "unconnected-(U800B-PD8{slash}FSMC_D13{slash}USART3_TX{slash}EVENTOUT-Pad55)") (class "Default")
      (node (ref "U800") (pin "55") (pinfunction "PD8/FSMC_D13/USART3_TX/EVENTOUT_55") (pintype "bidirectional"))
    )
    (net (code "83") (name "unconnected-(U800B-PD9{slash}FSMC_D14{slash}USART3_RX{slash}EVENTOUT-Pad56)") (class "Default")
      (node (ref "U800") (pin "56") (pinfunction "PD9/FSMC_D14/USART3_RX/EVENTOUT_56") (pintype "bidirectional"))
    )
    (net (code "84") (name "unconnected-(U800B-PD11{slash}FSMC_CLE{slash}FSMC_A16{slash}USART3_CTS{slash}EVENTOUT-Pad58)") (class "Default")
      (node (ref "U800") (pin "58") (pinfunction "PD11/FSMC_CLE/FSMC_A16/USART3_CTS/EVENTOUT_58") (pintype "bidirectional"))
    )
    (net (code "85") (name "unconnected-(U800B-PD12{slash}FSMC_ALE{slash}FSMC_A17{slash}TIM4_CH1{slash}USART3_RTS{slash}EVENTOUT-Pad59)") (class "Default")
      (node (ref "U800") (pin "59") (pinfunction "PD12/FSMC_ALE/FSMC_A17/TIM4_CH1/USART3_RTS/EVENTOUT_59") (pintype "bidirectional"))
    )
    (net (code "86") (name "unconnected-(U800B-PD13{slash}FSMC_A18{slash}TIM4_CH2{slash}EVENTOUT-Pad60)") (class "Default")
      (node (ref "U800") (pin "60") (pinfunction "PD13/FSMC_A18/TIM4_CH2/EVENTOUT_60") (pintype "bidirectional"))
    )
    (net (code "87") (name "unconnected-(U800B-PD14{slash}FSMC_D0{slash}TIM4_CH3{slash}EVENTOUT{slash}EVENTOUT-Pad61)") (class "Default")
      (node (ref "U800") (pin "61") (pinfunction "PD14/FSMC_D0/TIM4_CH3/EVENTOUT/EVENTOUT_61") (pintype "bidirectional"))
    )
    (net (code "88") (name "unconnected-(U800B-PD15{slash}FSMC_D1{slash}TIM4_CH4{slash}EVENTOUT-Pad62)") (class "Default")
      (node (ref "U800") (pin "62") (pinfunction "PD15/FSMC_D1/TIM4_CH4/EVENTOUT_62") (pintype "bidirectional"))
    )
    (net (code "89") (name "unconnected-(U800C-PE0{slash}TIM4_ETR{slash}FSMC_NBL0{slash}DCMI_D2{slash}EVENTOUT-Pad97)") (class "Default")
      (node (ref "U800") (pin "97") (pinfunction "PE0/TIM4_ETR/FSMC_NBL0/DCMI_D2/EVENTOUT_97") (pintype "bidirectional"))
    )
    (net (code "90") (name "unconnected-(U800C-PE1{slash}FSMC_NBL1{slash}DCMI_D3{slash}EVENTOUT-Pad98)") (class "Default")
      (node (ref "U800") (pin "98") (pinfunction "PE1/FSMC_NBL1/DCMI_D3/EVENTOUT_98") (pintype "bidirectional"))
    )
    (net (code "91") (name "unconnected-(U800C-PE6{slash}TRACED3{slash}FSMC_A22{slash}TIM9_CH2{slash}DCMI_D7{slash}EVENTOUT-Pad5)") (class "Default")
      (node (ref "U800") (pin "5") (pinfunction "PE6/TRACED3/FSMC_A22/TIM9_CH2/DCMI_D7/EVENTOUT_5") (pintype "bidirectional"))
    )
    (net (code "92") (name "unconnected-(U800C-PE7{slash}FSMC_D4{slash}TIM1_ETR{slash}EVENTOUT-Pad38)") (class "Default")
      (node (ref "U800") (pin "38") (pinfunction "PE7/FSMC_D4/TIM1_ETR/EVENTOUT_38") (pintype "bidirectional"))
    )
    (net (code "93") (name "unconnected-(U800C-PE8{slash}FSMC_D5{slash}TIM1_CH1N{slash}EVENTOUT-Pad39)") (class "Default")
      (node (ref "U800") (pin "39") (pinfunction "PE8/FSMC_D5/TIM1_CH1N/EVENTOUT_39") (pintype "bidirectional"))
    )
    (net (code "94") (name "unconnected-(U800C-PE9{slash}FSMC_D6{slash}TIM1_CH1{slash}EVENTOUT-Pad40)") (class "Default")
      (node (ref "U800") (pin "40") (pinfunction "PE9/FSMC_D6/TIM1_CH1/EVENTOUT_40") (pintype "bidirectional"))
    )
    (net (code "95") (name "unconnected-(U800C-PE10{slash}FSMC_D7{slash}TIM1_CH2N{slash}EVENTOUT-Pad41)") (class "Default")
      (node (ref "U800") (pin "41") (pinfunction "PE10/FSMC_D7/TIM1_CH2N/EVENTOUT_41") (pintype "bidirectional"))
    )
    (net (code "96") (name "unconnected-(U800C-PE11{slash}FSMC_D8{slash}TIM1_CH2{slash}EVENTOUT-Pad42)") (class "Default")
      (node (ref "U800") (pin "42") (pinfunction "PE11/FSMC_D8/TIM1_CH2/EVENTOUT_42") (pintype "bidirectional"))
    )
  )
)
